# Final_Project.net
KiCad netlist of a schematic drawn in Altium Designer
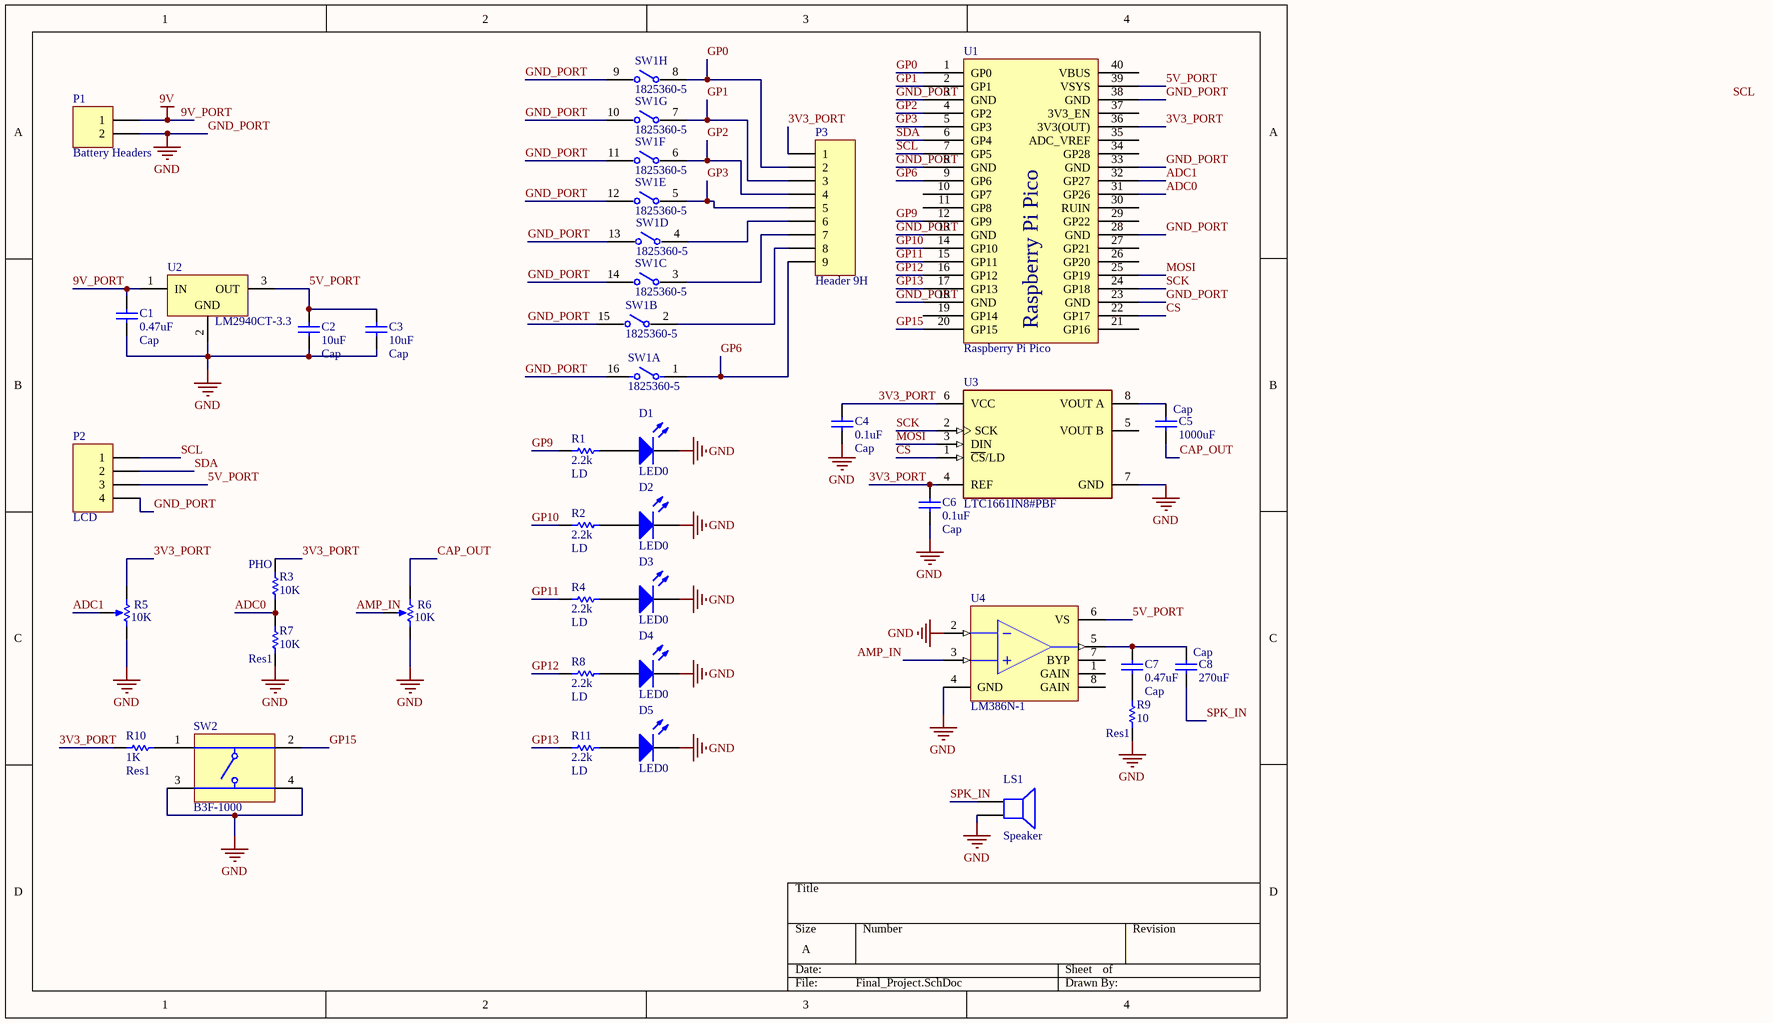
[diagram p0: Final_Project.SchDoc]

(export (version "E")
  (design (tool "Eeschema 10.0.6"))
  (components
    (comp (ref "C1")
      (value "Cap")
      (footprint "RAD-0.3")
      (description "Capacitor")
      (fields (field (name "ALTIUM_VALUE") "0.47uF") (field (name "PUBLISHER") "Altium Limited"))
      (libsource (lib "Miscellaneous Devices") (part "Cap"))
    )
    (comp (ref "C2")
      (value "Cap")
      (footprint "RAD-0.3")
      (description "Capacitor")
      (fields (field (name "ALTIUM_VALUE") "10uF") (field (name "PUBLISHER") "Altium Limited"))
      (libsource (lib "Miscellaneous Devices") (part "Cap"))
    )
    (comp (ref "C3")
      (value "Cap")
      (footprint "RAD-0.3")
      (description "Capacitor")
      (fields (field (name "ALTIUM_VALUE") "10uF") (field (name "PUBLISHER") "Altium Limited"))
      (libsource (lib "Miscellaneous Devices") (part "Cap"))
    )
    (comp (ref "C4")
      (value "Cap")
      (footprint "RAD-0.3")
      (description "Capacitor")
      (fields (field (name "ALTIUM_VALUE") "0.1uF") (field (name "PUBLISHER") "Altium Limited"))
      (libsource (lib "Miscellaneous Devices") (part "Cap"))
    )
    (comp (ref "C5")
      (value "Cap")
      (footprint "RAD-0.3")
      (description "Capacitor")
      (fields (field (name "ALTIUM_VALUE") "1000uF") (field (name "PUBLISHER") "Altium Limited"))
      (libsource (lib "Miscellaneous Devices") (part "Cap"))
    )
    (comp (ref "C6")
      (value "Cap")
      (footprint "RAD-0.3")
      (description "Capacitor")
      (fields (field (name "ALTIUM_VALUE") "0.1uF") (field (name "PUBLISHER") "Altium Limited"))
      (libsource (lib "Miscellaneous Devices") (part "Cap"))
    )
    (comp (ref "C7")
      (value "Cap")
      (footprint "RAD-0.3")
      (description "Capacitor")
      (fields (field (name "ALTIUM_VALUE") "0.47uF") (field (name "PUBLISHER") "Altium Limited"))
      (libsource (lib "Miscellaneous Devices") (part "Cap"))
    )
    (comp (ref "C8")
      (value "Cap")
      (footprint "RAD-0.3")
      (description "Capacitor")
      (fields (field (name "ALTIUM_VALUE") "270uF") (field (name "PUBLISHER") "Altium Limited"))
      (libsource (lib "Miscellaneous Devices") (part "Cap"))
    )
    (comp (ref "D1")
      (value "LED0")
      (footprint "LED-0")
      (description "Typical INFRARED GaAs LED")
      (fields (field (name "PUBLISHER") "Altium Limited"))
      (libsource (lib "Miscellaneous Devices") (part "LED0"))
    )
    (comp (ref "D2")
      (value "LED0")
      (footprint "LED-0")
      (description "Typical INFRARED GaAs LED")
      (fields (field (name "PUBLISHER") "Altium Limited"))
      (libsource (lib "Miscellaneous Devices") (part "LED0"))
    )
    (comp (ref "D3")
      (value "LED0")
      (footprint "LED-0")
      (description "Typical INFRARED GaAs LED")
      (fields (field (name "PUBLISHER") "Altium Limited"))
      (libsource (lib "Miscellaneous Devices") (part "LED0"))
    )
    (comp (ref "D4")
      (value "LED0")
      (footprint "LED-0")
      (description "Typical INFRARED GaAs LED")
      (fields (field (name "PUBLISHER") "Altium Limited"))
      (libsource (lib "Miscellaneous Devices") (part "LED0"))
    )
    (comp (ref "D5")
      (value "LED0")
      (footprint "LED-0")
      (description "Typical INFRARED GaAs LED")
      (fields (field (name "PUBLISHER") "Altium Limited"))
      (libsource (lib "Miscellaneous Devices") (part "LED0"))
    )
    (comp (ref "LS1")
      (value "Speaker")
      (footprint "PIN2")
      (description "Loudspeaker")
      (fields (field (name "PUBLISHER") "Altium Limited"))
      (libsource (lib "Miscellaneous Devices") (part "Speaker"))
    )
    (comp (ref "P1")
      (value "Battery Headers")
      (footprint "HDR1X2")
      (description "Header, 2-Pin")
      (fields (field (name "PUBLISHER") "Altium Limited"))
      (libsource (lib "Miscellaneous Connectors") (part "Header 2"))
    )
    (comp (ref "P2")
      (value "LCD")
      (footprint "HDR1X4")
      (description "Header, 4-Pin")
      (fields (field (name "PUBLISHER") "Altium Limited"))
      (libsource (lib "Miscellaneous Connectors") (part "Header 4"))
    )
    (comp (ref "P3")
      (value "Header 9H")
      (footprint "HDR1X9H")
      (description "Header, 9-Pin, Right Angle")
      (fields (field (name "PUBLISHER") "Altium Limited"))
      (libsource (lib "Miscellaneous Connectors") (part "Header 9H"))
    )
    (comp (ref "R1")
      (value "LD")
      (footprint "AXIAL-0.3")
      (description "Resistor")
      (fields (field (name "ALTIUM_VALUE") "2.2k") (field (name "PUBLISHER") "Altium Limited"))
      (libsource (lib "Miscellaneous Devices") (part "Res1"))
    )
    (comp (ref "R2")
      (value "LD")
      (footprint "AXIAL-0.3")
      (description "Resistor")
      (fields (field (name "ALTIUM_VALUE") "2.2k") (field (name "PUBLISHER") "Altium Limited"))
      (libsource (lib "Miscellaneous Devices") (part "Res1"))
    )
    (comp (ref "R3")
      (value "PHO")
      (footprint "AXIAL-0.3")
      (description "Resistor")
      (fields (field (name "ALTIUM_VALUE") "10K") (field (name "PUBLISHER") "Altium Limited"))
      (libsource (lib "Miscellaneous Devices") (part "Res1"))
    )
    (comp (ref "R4")
      (value "LD")
      (footprint "AXIAL-0.3")
      (description "Resistor")
      (fields (field (name "ALTIUM_VALUE") "2.2k") (field (name "PUBLISHER") "Altium Limited"))
      (libsource (lib "Miscellaneous Devices") (part "Res1"))
    )
    (comp (ref "R5")
      (value "10K")
      (footprint "POT inline wide")
      (description "Potentiometer")
      (fields (field (name "Comment") "RPot_1") (field (name "PUBLISHER") "Altium Limited"))
      (libsource (lib "ECE Lib 22") (part "RPot_3"))
    )
    (comp (ref "R6")
      (value "10K")
      (footprint "POT inline wide")
      (description "Potentiometer")
      (fields (field (name "Comment") "RPot_1") (field (name "PUBLISHER") "Altium Limited"))
      (libsource (lib "ECE Lib 22") (part "RPot_3"))
    )
    (comp (ref "R7")
      (value "Res1")
      (footprint "AXIAL-0.3")
      (description "Resistor")
      (fields (field (name "ALTIUM_VALUE") "10K") (field (name "PUBLISHER") "Altium Limited"))
      (libsource (lib "Miscellaneous Devices") (part "Res1"))
    )
    (comp (ref "R8")
      (value "LD")
      (footprint "AXIAL-0.3")
      (description "Resistor")
      (fields (field (name "ALTIUM_VALUE") "2.2k") (field (name "PUBLISHER") "Altium Limited"))
      (libsource (lib "Miscellaneous Devices") (part "Res1"))
    )
    (comp (ref "R9")
      (value "Res1")
      (footprint "AXIAL-0.3")
      (description "Resistor")
      (fields (field (name "ALTIUM_VALUE") "10") (field (name "PUBLISHER") "Altium Limited"))
      (libsource (lib "Miscellaneous Devices") (part "Res1"))
    )
    (comp (ref "R10")
      (value "Res1")
      (footprint "AXIAL-0.3")
      (description "Resistor")
      (fields (field (name "ALTIUM_VALUE") "1K") (field (name "PUBLISHER") "Altium Limited"))
      (libsource (lib "Miscellaneous Devices") (part "Res1"))
    )
    (comp (ref "R11")
      (value "LD")
      (footprint "AXIAL-0.3")
      (description "Resistor")
      (fields (field (name "ALTIUM_VALUE") "2.2k") (field (name "PUBLISHER") "Altium Limited"))
      (libsource (lib "Miscellaneous Devices") (part "Res1"))
    )
    (comp (ref "SW1")
      (value "1825360-5")
      (footprint "FP-1825360-5-MFG")
      (description "SWITCH SLIDE DIP SPST 100MA 24V")
      (libsource (lib "Components - 06.04.26 - 13.49") (part "CMP-03400-000027-1"))
    )
    (comp (ref "SW2")
      (value "B3F-1000")
      (footprint "OMRON-B3F-1000-4_V")
      (description "Tactile Switch, SPST-NO, 0.05 A, 5 to 24 V, -25 to 70 degC, 4-Pin THD, RoHS, Bulk")
      (libsource (lib "switch") (part "CMP-1677-00002-1"))
    )
    (comp (ref "U1")
      (value "Raspberry Pi Pico")
      (footprint "Raspberry Pi Pico")
      (libsource (lib "ECE Lib 22") (part "Raspberry Pi Pico"))
    )
    (comp (ref "U2")
      (value "LM2940CT-3.3")
      (footprint "T03B")
      (description "1A Low Dropout Regulator, 3-pin TO-220")
      (fields (field (name "MANUFACTURER") "National Semiconductor"))
      (libsource (lib "ECE Lib 22") (part "LM2940CT-5.0"))
    )
    (comp (ref "U3")
      (value "LTC1661IN8#PBF")
      (footprint "FP-N-8-05-08-1510-MFG")
      (description "LTC1661IN8#PBF Dual Serial Input Loading 30 Us Settling Time 10-BIT Dac PDIP8")
      (libsource (lib "DAC") (part "CMP-00026-88317689-1"))
    )
    (comp (ref "U4")
      (value "LM386N-1")
      (footprint "DIP-8")
      (description "Low-Voltage Audio Power Amplifier")
      (fields (field (name "PUBLISHER") "Altium Limited"))
      (libsource (lib "ECE Lib 22") (part "LM386N-1"))
    )
  )
  (nets
    (net (code "1") (name "/3V3_PORT") (class "Default")
      (node (ref "C4") (pin "2") (pinfunction "2_2") (pintype "passive"))
      (node (ref "C6") (pin "2") (pinfunction "2_2") (pintype "passive"))
      (node (ref "P3") (pin "1") (pinfunction "1_1") (pintype "passive"))
      (node (ref "R10") (pin "1") (pinfunction "1_1") (pintype "passive"))
      (node (ref "R3") (pin "2") (pinfunction "2_2") (pintype "passive"))
      (node (ref "R5") (pin "1") (pinfunction "TOP_1") (pintype "passive"))
      (node (ref "U1") (pin "36") (pinfunction "3V3(OUT)_36") (pintype "passive"))
      (node (ref "U3") (pin "4") (pinfunction "REF_4") (pintype "passive"))
      (node (ref "U3") (pin "6") (pinfunction "VCC_6") (pintype "power_in"))
    )
    (net (code "2") (name "/5V_PORT") (class "Default")
      (node (ref "C2") (pin "2") (pinfunction "2_2") (pintype "passive"))
      (node (ref "C3") (pin "2") (pinfunction "2_2") (pintype "passive"))
      (node (ref "P2") (pin "3") (pinfunction "3_3") (pintype "passive"))
      (node (ref "U1") (pin "39") (pinfunction "VSYS_39") (pintype "passive"))
      (node (ref "U2") (pin "3") (pinfunction "OUT_3") (pintype "power_in"))
      (node (ref "U4") (pin "6") (pinfunction "VS_6") (pintype "power_in"))
    )
    (net (code "3") (name "/ADC0") (class "Default")
      (node (ref "R3") (pin "1") (pinfunction "1_1") (pintype "passive"))
      (node (ref "R7") (pin "2") (pinfunction "2_2") (pintype "passive"))
      (node (ref "U1") (pin "31") (pinfunction "GP26_31") (pintype "passive"))
    )
    (net (code "4") (name "/ADC1") (class "Default")
      (node (ref "R5") (pin "2") (pinfunction "TAP_2") (pintype "passive"))
      (node (ref "U1") (pin "32") (pinfunction "GP27_32") (pintype "passive"))
    )
    (net (code "5") (name "/AMP_IN") (class "Default")
      (node (ref "R6") (pin "2") (pinfunction "TAP_2") (pintype "passive"))
      (node (ref "U4") (pin "3") (pinfunction "IN+_3") (pintype "input"))
    )
    (net (code "6") (name "/CAP_OUT") (class "Default")
      (node (ref "C5") (pin "1") (pinfunction "1_1") (pintype "passive"))
      (node (ref "R6") (pin "1") (pinfunction "TOP_1") (pintype "passive"))
    )
    (net (code "7") (name "/CS") (class "Default")
      (node (ref "U1") (pin "22") (pinfunction "GP17_22") (pintype "passive"))
      (node (ref "U3") (pin "1") (pinfunction "~{CS}/LD_1") (pintype "input"))
    )
    (net (code "8") (name "/GP0") (class "Default")
      (node (ref "P3") (pin "2") (pinfunction "2_2") (pintype "passive"))
      (node (ref "SW1") (pin "8") (pinfunction "8_8") (pintype "passive"))
      (node (ref "U1") (pin "1") (pinfunction "GP0_1") (pintype "passive"))
    )
    (net (code "9") (name "/GP1") (class "Default")
      (node (ref "P3") (pin "3") (pinfunction "3_3") (pintype "passive"))
      (node (ref "SW1") (pin "7") (pinfunction "7_7") (pintype "passive"))
      (node (ref "U1") (pin "2") (pinfunction "GP1_2") (pintype "passive"))
    )
    (net (code "10") (name "/GP2") (class "Default")
      (node (ref "P3") (pin "4") (pinfunction "4_4") (pintype "passive"))
      (node (ref "SW1") (pin "6") (pinfunction "6_6") (pintype "passive"))
      (node (ref "U1") (pin "4") (pinfunction "GP2_4") (pintype "passive"))
    )
    (net (code "11") (name "/GP3") (class "Default")
      (node (ref "P3") (pin "5") (pinfunction "5_5") (pintype "passive"))
      (node (ref "SW1") (pin "5") (pinfunction "5_5") (pintype "passive"))
      (node (ref "U1") (pin "5") (pinfunction "GP3_5") (pintype "passive"))
    )
    (net (code "12") (name "/GP6") (class "Default")
      (node (ref "P3") (pin "9") (pinfunction "9_9") (pintype "passive"))
      (node (ref "SW1") (pin "1") (pinfunction "1_1") (pintype "passive"))
      (node (ref "U1") (pin "9") (pinfunction "GP6_9") (pintype "passive"))
    )
    (net (code "13") (name "/GP9") (class "Default")
      (node (ref "R1") (pin "2") (pinfunction "2_2") (pintype "passive"))
      (node (ref "U1") (pin "12") (pinfunction "GP9_12") (pintype "passive"))
    )
    (net (code "14") (name "/GP10") (class "Default")
      (node (ref "R2") (pin "2") (pinfunction "2_2") (pintype "passive"))
      (node (ref "U1") (pin "14") (pinfunction "GP10_14") (pintype "passive"))
    )
    (net (code "15") (name "/GP11") (class "Default")
      (node (ref "R4") (pin "2") (pinfunction "2_2") (pintype "passive"))
      (node (ref "U1") (pin "15") (pinfunction "GP11_15") (pintype "passive"))
    )
    (net (code "16") (name "/GP12") (class "Default")
      (node (ref "R8") (pin "2") (pinfunction "2_2") (pintype "passive"))
      (node (ref "U1") (pin "16") (pinfunction "GP12_16") (pintype "passive"))
    )
    (net (code "17") (name "/GP13") (class "Default")
      (node (ref "R11") (pin "2") (pinfunction "2_2") (pintype "passive"))
      (node (ref "U1") (pin "17") (pinfunction "GP13_17") (pintype "passive"))
    )
    (net (code "18") (name "/GP15") (class "Default")
      (node (ref "SW2") (pin "2") (pinfunction "2_2") (pintype "passive"))
      (node (ref "U1") (pin "20") (pinfunction "GP15_20") (pintype "passive"))
    )
    (net (code "19") (name "/MOSI") (class "Default")
      (node (ref "U1") (pin "25") (pinfunction "GP19_25") (pintype "passive"))
      (node (ref "U3") (pin "3") (pinfunction "DIN_3") (pintype "input"))
    )
    (net (code "20") (name "/SCK") (class "Default")
      (node (ref "U1") (pin "24") (pinfunction "GP18_24") (pintype "passive"))
      (node (ref "U3") (pin "2") (pinfunction "SCK_2") (pintype "input"))
    )
    (net (code "21") (name "/SCL") (class "Default")
      (node (ref "P2") (pin "1") (pinfunction "1_1") (pintype "passive"))
      (node (ref "U1") (pin "7") (pinfunction "GP5_7") (pintype "passive"))
    )
    (net (code "22") (name "/SDA") (class "Default")
      (node (ref "P2") (pin "2") (pinfunction "2_2") (pintype "passive"))
      (node (ref "U1") (pin "6") (pinfunction "GP4_6") (pintype "passive"))
    )
    (net (code "23") (name "/SPK_IN") (class "Default")
      (node (ref "C8") (pin "1") (pinfunction "1_1") (pintype "passive"))
      (node (ref "LS1") (pin "1") (pinfunction "1_1") (pintype "passive"))
    )
    (net (code "24") (name "9V") (class "Default")
      (node (ref "C1") (pin "2") (pinfunction "2_2") (pintype "passive"))
      (node (ref "P1") (pin "1") (pinfunction "1_1") (pintype "passive"))
      (node (ref "U2") (pin "1") (pinfunction "IN_1") (pintype "power_in"))
    )
    (net (code "25") (name "GND") (class "Default")
      (node (ref "C1") (pin "1") (pinfunction "1_1") (pintype "passive"))
      (node (ref "C2") (pin "1") (pinfunction "1_1") (pintype "passive"))
      (node (ref "C3") (pin "1") (pinfunction "1_1") (pintype "passive"))
      (node (ref "C4") (pin "1") (pinfunction "1_1") (pintype "passive"))
      (node (ref "C6") (pin "1") (pinfunction "1_1") (pintype "passive"))
      (node (ref "D1") (pin "2") (pinfunction "K_2") (pintype "passive"))
      (node (ref "D2") (pin "2") (pinfunction "K_2") (pintype "passive"))
      (node (ref "D3") (pin "2") (pinfunction "K_2") (pintype "passive"))
      (node (ref "D4") (pin "2") (pinfunction "K_2") (pintype "passive"))
      (node (ref "D5") (pin "2") (pinfunction "K_2") (pintype "passive"))
      (node (ref "LS1") (pin "2") (pinfunction "2_2") (pintype "passive"))
      (node (ref "P1") (pin "2") (pinfunction "2_2") (pintype "passive"))
      (node (ref "P2") (pin "4") (pinfunction "4_4") (pintype "passive"))
      (node (ref "R5") (pin "3") (pinfunction "BOT_3") (pintype "passive"))
      (node (ref "R6") (pin "3") (pinfunction "BOT_3") (pintype "passive"))
      (node (ref "R7") (pin "1") (pinfunction "1_1") (pintype "passive"))
      (node (ref "R9") (pin "1") (pinfunction "1_1") (pintype "passive"))
      (node (ref "SW1") (pin "10") (pinfunction "10_10") (pintype "passive"))
      (node (ref "SW1") (pin "11") (pinfunction "11_11") (pintype "passive"))
      (node (ref "SW1") (pin "12") (pinfunction "12_12") (pintype "passive"))
      (node (ref "SW1") (pin "13") (pinfunction "13_13") (pintype "passive"))
      (node (ref "SW1") (pin "14") (pinfunction "14_14") (pintype "passive"))
      (node (ref "SW1") (pin "15") (pinfunction "15_15") (pintype "passive"))
      (node (ref "SW1") (pin "16") (pinfunction "16_16") (pintype "passive"))
      (node (ref "SW1") (pin "9") (pinfunction "9_9") (pintype "passive"))
      (node (ref "SW2") (pin "3") (pinfunction "3_3") (pintype "passive"))
      (node (ref "SW2") (pin "4") (pinfunction "4_4") (pintype "passive"))
      (node (ref "U1") (pin "13") (pinfunction "GND_13") (pintype "passive"))
      (node (ref "U1") (pin "18") (pinfunction "GND_18") (pintype "passive"))
      (node (ref "U1") (pin "23") (pinfunction "GND_23") (pintype "passive"))
      (node (ref "U1") (pin "28") (pinfunction "GND_28") (pintype "passive"))
      (node (ref "U1") (pin "3") (pinfunction "GND_3") (pintype "passive"))
      (node (ref "U1") (pin "33") (pinfunction "GND_33") (pintype "passive"))
      (node (ref "U1") (pin "38") (pinfunction "GND_38") (pintype "passive"))
      (node (ref "U1") (pin "8") (pinfunction "GND_8") (pintype "passive"))
      (node (ref "U2") (pin "2") (pinfunction "GND_2") (pintype "power_in"))
      (node (ref "U3") (pin "7") (pinfunction "GND_7") (pintype "power_in"))
      (node (ref "U4") (pin "2") (pinfunction "IN-_2") (pintype "input"))
      (node (ref "U4") (pin "4") (pinfunction "GND_4") (pintype "power_in"))
    )
    (net (code "26") (name "Net-(C7-Pad1)") (class "Default")
      (node (ref "C7") (pin "1") (pinfunction "1_1") (pintype "passive"))
      (node (ref "R9") (pin "2") (pinfunction "2_2") (pintype "passive"))
    )
    (net (code "27") (name "Net-(D1-A)") (class "Default")
      (node (ref "D1") (pin "1") (pinfunction "A_1") (pintype "passive"))
      (node (ref "R1") (pin "1") (pinfunction "1_1") (pintype "passive"))
    )
    (net (code "28") (name "Net-(D2-A)") (class "Default")
      (node (ref "D2") (pin "1") (pinfunction "A_1") (pintype "passive"))
      (node (ref "R2") (pin "1") (pinfunction "1_1") (pintype "passive"))
    )
    (net (code "29") (name "Net-(D3-A)") (class "Default")
      (node (ref "D3") (pin "1") (pinfunction "A_1") (pintype "passive"))
      (node (ref "R4") (pin "1") (pinfunction "1_1") (pintype "passive"))
    )
    (net (code "30") (name "Net-(D4-A)") (class "Default")
      (node (ref "D4") (pin "1") (pinfunction "A_1") (pintype "passive"))
      (node (ref "R8") (pin "1") (pinfunction "1_1") (pintype "passive"))
    )
    (net (code "31") (name "Net-(D5-A)") (class "Default")
      (node (ref "D5") (pin "1") (pinfunction "A_1") (pintype "passive"))
      (node (ref "R11") (pin "1") (pinfunction "1_1") (pintype "passive"))
    )
    (net (code "32") (name "Net-(P3-Pad6)") (class "Default")
      (node (ref "P3") (pin "6") (pinfunction "6_6") (pintype "passive"))
      (node (ref "SW1") (pin "4") (pinfunction "4_4") (pintype "passive"))
    )
    (net (code "33") (name "Net-(P3-Pad7)") (class "Default")
      (node (ref "P3") (pin "7") (pinfunction "7_7") (pintype "passive"))
      (node (ref "SW1") (pin "3") (pinfunction "3_3") (pintype "passive"))
    )
    (net (code "34") (name "Net-(P3-Pad8)") (class "Default")
      (node (ref "P3") (pin "8") (pinfunction "8_8") (pintype "passive"))
      (node (ref "SW1") (pin "2") (pinfunction "2_2") (pintype "passive"))
    )
    (net (code "35") (name "Net-(R10-Pad2)") (class "Default")
      (node (ref "R10") (pin "2") (pinfunction "2_2") (pintype "passive"))
      (node (ref "SW2") (pin "1") (pinfunction "1_1") (pintype "passive"))
    )
    (net (code "36") (name "Net-(U3-VOUT_A)") (class "Default")
      (node (ref "C5") (pin "2") (pinfunction "2_2") (pintype "passive"))
      (node (ref "U3") (pin "8") (pinfunction "VOUT_A_8") (pintype "passive"))
    )
    (net (code "37") (name "Net-(U4-OUT)") (class "Default")
      (node (ref "C7") (pin "2") (pinfunction "2_2") (pintype "passive"))
      (node (ref "C8") (pin "2") (pinfunction "2_2") (pintype "passive"))
      (node (ref "U4") (pin "5") (pinfunction "OUT_5") (pintype "output"))
    )
    (net (code "38") (name "unconnected-(U1-3V3_EN-Pad37)") (class "Default")
      (node (ref "U1") (pin "37") (pinfunction "3V3_EN_37") (pintype "passive"))
    )
    (net (code "39") (name "unconnected-(U1-ADC_VREF-Pad35)") (class "Default")
      (node (ref "U1") (pin "35") (pinfunction "ADC_VREF_35") (pintype "passive"))
    )
    (net (code "40") (name "unconnected-(U1-GP7-Pad10)") (class "Default")
      (node (ref "U1") (pin "10") (pinfunction "GP7_10") (pintype "passive"))
    )
    (net (code "41") (name "unconnected-(U1-GP8-Pad11)") (class "Default")
      (node (ref "U1") (pin "11") (pinfunction "GP8_11") (pintype "passive"))
    )
    (net (code "42") (name "unconnected-(U1-GP14-Pad19)") (class "Default")
      (node (ref "U1") (pin "19") (pinfunction "GP14_19") (pintype "passive"))
    )
    (net (code "43") (name "unconnected-(U1-GP16-Pad21)") (class "Default")
      (node (ref "U1") (pin "21") (pinfunction "GP16_21") (pintype "passive"))
    )
    (net (code "44") (name "unconnected-(U1-GP20-Pad26)") (class "Default")
      (node (ref "U1") (pin "26") (pinfunction "GP20_26") (pintype "passive"))
    )
    (net (code "45") (name "unconnected-(U1-GP21-Pad27)") (class "Default")
      (node (ref "U1") (pin "27") (pinfunction "GP21_27") (pintype "passive"))
    )
    (net (code "46") (name "unconnected-(U1-GP22-Pad29)") (class "Default")
      (node (ref "U1") (pin "29") (pinfunction "GP22_29") (pintype "passive"))
    )
    (net (code "47") (name "unconnected-(U1-GP28-Pad34)") (class "Default")
      (node (ref "U1") (pin "34") (pinfunction "GP28_34") (pintype "passive"))
    )
    (net (code "48") (name "unconnected-(U1-RUIN-Pad30)") (class "Default")
      (node (ref "U1") (pin "30") (pinfunction "RUIN_30") (pintype "passive"))
    )
    (net (code "49") (name "unconnected-(U1-VBUS-Pad40)") (class "Default")
      (node (ref "U1") (pin "40") (pinfunction "VBUS_40") (pintype "passive"))
    )
    (net (code "50") (name "unconnected-(U3-VOUT_B-Pad5)") (class "Default")
      (node (ref "U3") (pin "5") (pinfunction "VOUT_B_5") (pintype "passive"))
    )
    (net (code "51") (name "unconnected-(U4-BYP-Pad7)") (class "Default")
      (node (ref "U4") (pin "7") (pinfunction "BYP_7") (pintype "passive"))
    )
    (net (code "52") (name "unconnected-(U4-GAIN-Pad1)") (class "Default")
      (node (ref "U4") (pin "1") (pinfunction "GAIN_1") (pintype "passive"))
    )
    (net (code "53") (name "unconnected-(U4-GAIN-Pad8)") (class "Default")
      (node (ref "U4") (pin "8") (pinfunction "GAIN_8") (pintype "passive"))
    )
  )
)
